# LightLog_SMD_0_7B.net
KiCad netlist of a schematic drawn in EAGLE
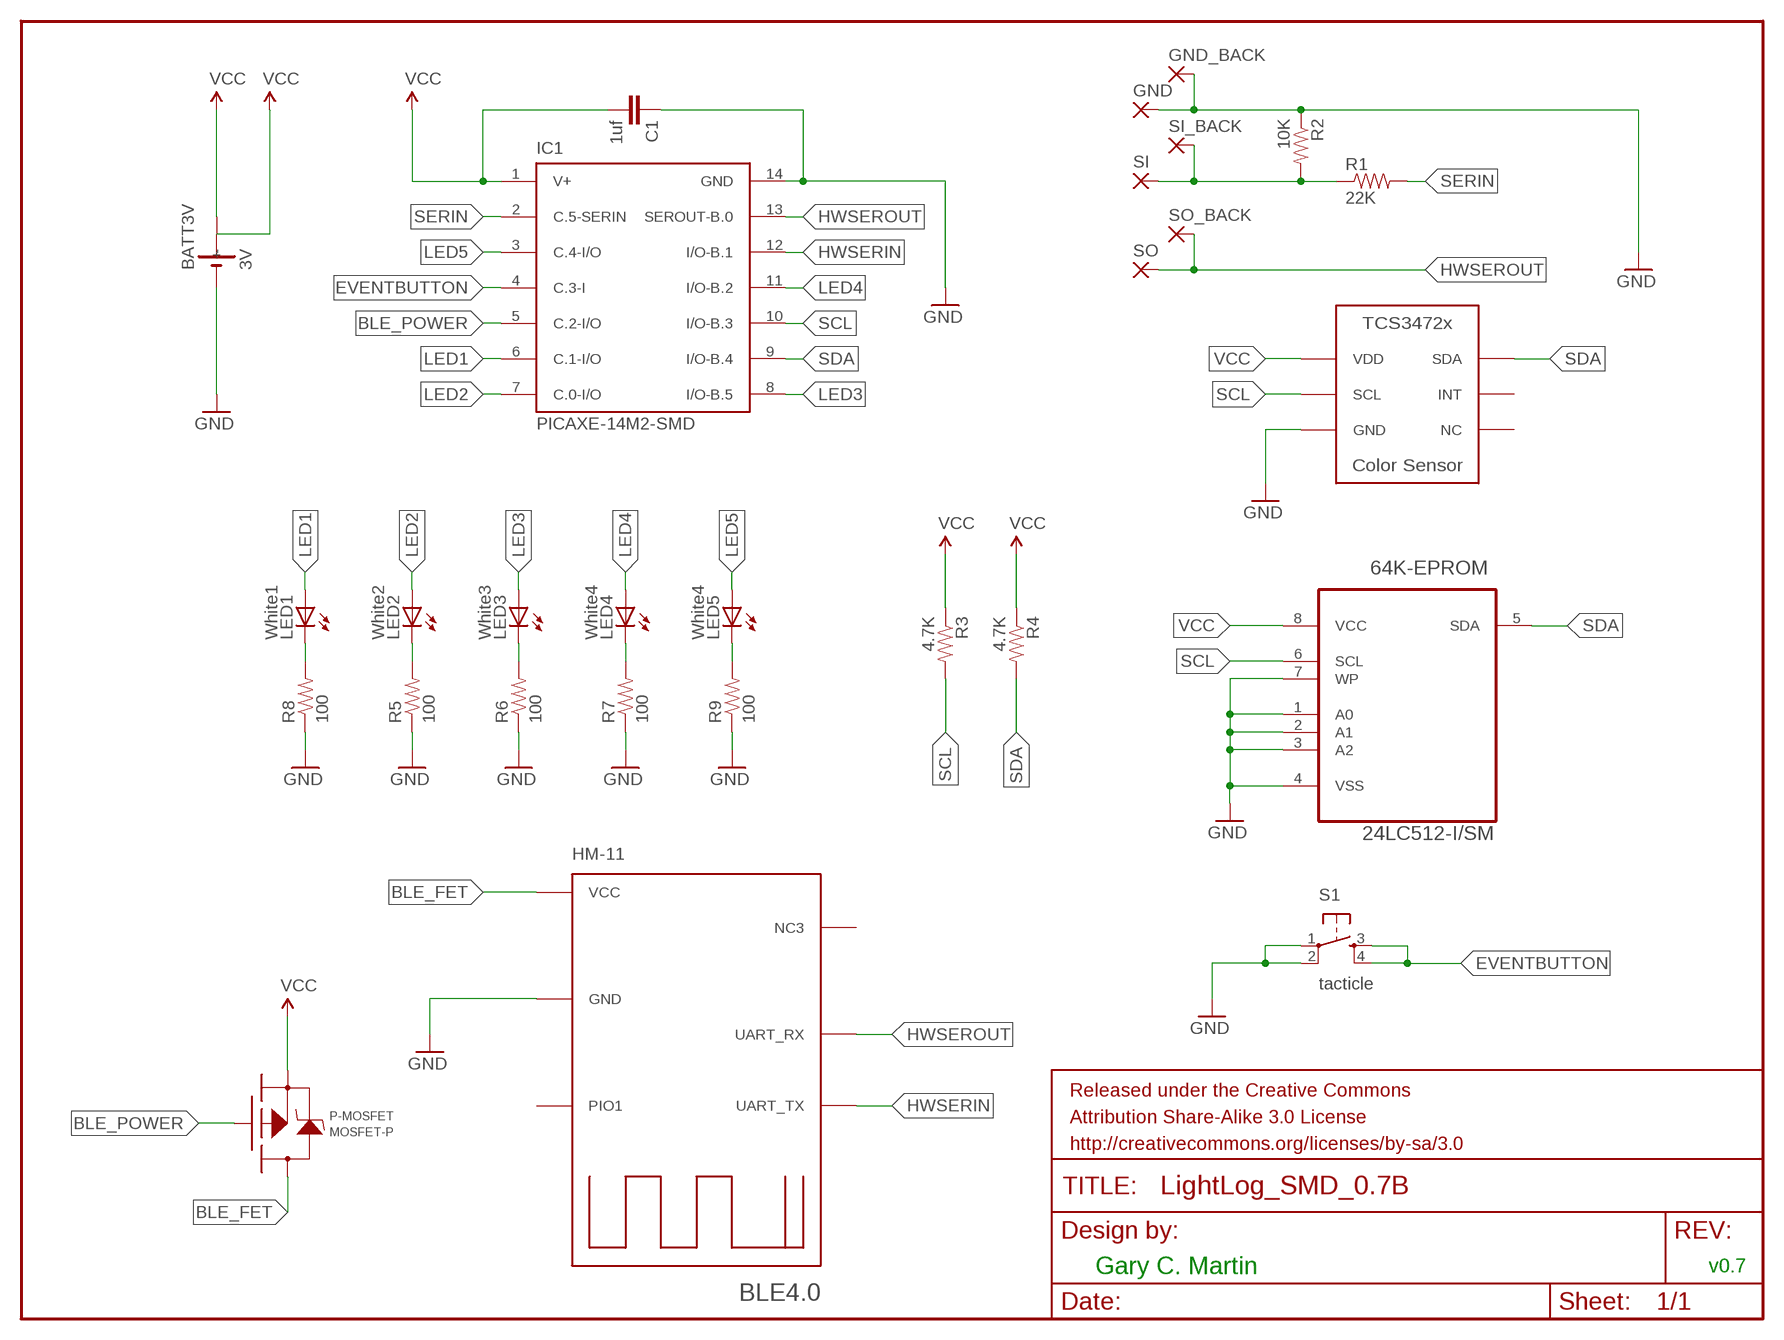
[diagram p0: schematic, sheet 1]

(export (version "E")
  (design (tool "Eeschema 10.0.6"))
  (components
    (comp (ref "64K-EPROM")
      (value "24LC512-I/SM")
      (footprint "eagle-import:SOIC127P794X203-8N")
      (libsource (lib "eagle-import") (part "24LC512-I/SM"))
    )
    (comp (ref "BATT3V")
      (value "3V")
      (footprint "eagle-import:BAT-HLD-001-CR2032-SMD")
      (libsource (lib "eagle-import") (part "BAT-HLD-001-CR2032"))
    )
    (comp (ref "BLE4.0")
      (value "HM-11")
      (footprint "eagle-import:HM-11-MIN")
      (libsource (lib "eagle-import") (part "HM-11-MIN"))
    )
    (comp (ref "C1")
      (value "1uf")
      (footprint "eagle-import:0805")
      (libsource (lib "eagle-import") (part "CAP0805"))
    )
    (comp (ref "GND")
      (value "SMD2")
      (footprint "eagle-import:SMD1,27-2,54")
      (libsource (lib "eagle-import") (part "SMD2"))
    )
    (comp (ref "GND_BACK")
      (value "SMD2")
      (footprint "eagle-import:SMD1,27-2,54")
      (libsource (lib "eagle-import") (part "SMD2"))
    )
    (comp (ref "IC1")
      (value "PICAXE-14M2-SMD")
      (footprint "eagle-import:SOIC14")
      (libsource (lib "eagle-import") (part "PICAXE-14M2-SMD"))
    )
    (comp (ref "LED1")
      (value "White1")
      (footprint "eagle-import:LED-0603")
      (libsource (lib "eagle-import") (part "LED0603"))
    )
    (comp (ref "LED2")
      (value "White2")
      (footprint "eagle-import:LED-0603")
      (libsource (lib "eagle-import") (part "LED0603"))
    )
    (comp (ref "LED3")
      (value "White3")
      (footprint "eagle-import:LED-0603")
      (libsource (lib "eagle-import") (part "LED0603"))
    )
    (comp (ref "LED4")
      (value "White4")
      (footprint "eagle-import:LED-0603")
      (libsource (lib "eagle-import") (part "LED0603"))
    )
    (comp (ref "LED5")
      (value "White4")
      (footprint "eagle-import:LED-0603")
      (libsource (lib "eagle-import") (part "LED0603"))
    )
    (comp (ref "P-MOSFET")
      (value "MOSFET-P")
      (footprint "eagle-import:SOT23-R")
      (libsource (lib "eagle-import") (part "MOSFET-P"))
    )
    (comp (ref "R1")
      (value "22K")
      (footprint "eagle-import:0805")
      (libsource (lib "eagle-import") (part "RESISTOR0805-RES"))
    )
    (comp (ref "R2")
      (value "10K")
      (footprint "eagle-import:0805")
      (libsource (lib "eagle-import") (part "RESISTOR0805-RES"))
    )
    (comp (ref "R3")
      (value "4.7K")
      (footprint "eagle-import:0805")
      (libsource (lib "eagle-import") (part "RESISTOR0805-RES"))
    )
    (comp (ref "R4")
      (value "4.7K")
      (footprint "eagle-import:0805")
      (libsource (lib "eagle-import") (part "RESISTOR0805-RES"))
    )
    (comp (ref "R5")
      (value "100")
      (footprint "eagle-import:0805")
      (libsource (lib "eagle-import") (part "RESISTOR0805-RES"))
    )
    (comp (ref "R6")
      (value "100")
      (footprint "eagle-import:0805")
      (libsource (lib "eagle-import") (part "RESISTOR0805-RES"))
    )
    (comp (ref "R7")
      (value "100")
      (footprint "eagle-import:0805")
      (libsource (lib "eagle-import") (part "RESISTOR0805-RES"))
    )
    (comp (ref "R8")
      (value "100")
      (footprint "eagle-import:0805")
      (libsource (lib "eagle-import") (part "RESISTOR0805-RES"))
    )
    (comp (ref "R9")
      (value "100")
      (footprint "eagle-import:0805")
      (libsource (lib "eagle-import") (part "RESISTOR0805-RES"))
    )
    (comp (ref "S1")
      (value "tacticle")
      (footprint "eagle-import:TACTILE_SWITCH_SMD")
      (libsource (lib "eagle-import") (part "TAC_SWITCHSMD"))
    )
    (comp (ref "SI")
      (value "SMD2")
      (footprint "eagle-import:SMD1,27-2,54")
      (libsource (lib "eagle-import") (part "SMD2"))
    )
    (comp (ref "SI_BACK")
      (value "SMD2")
      (footprint "eagle-import:SMD1,27-2,54")
      (libsource (lib "eagle-import") (part "SMD2"))
    )
    (comp (ref "SO")
      (value "SMD2")
      (footprint "eagle-import:SMD1,27-2,54")
      (libsource (lib "eagle-import") (part "SMD2"))
    )
    (comp (ref "SO_BACK")
      (value "SMD2")
      (footprint "eagle-import:SMD1,27-2,54")
      (libsource (lib "eagle-import") (part "SMD2"))
    )
    (comp (ref "U$1")
      (value "TCS3472")
      (footprint "eagle-import:DUAL-FLAT-NO-LEAD-6PIN")
      (libsource (lib "eagle-import") (part "TCS3472"))
    )
  )
  (nets
    (net (code "1") (name "BLE_FET") (class "Default")
      (node (ref "BLE4.0") (pin "VCC") (pinfunction "VCC_VCC") (pintype "bidirectional"))
      (node (ref "P-MOSFET") (pin "3") (pinfunction "D_3") (pintype "passive"))
    )
    (net (code "2") (name "BLE_POWER") (class "Default")
      (node (ref "IC1") (pin "5") (pinfunction "C.2-I/O_5") (pintype "bidirectional"))
      (node (ref "P-MOSFET") (pin "1") (pinfunction "G_1") (pintype "passive"))
    )
    (net (code "3") (name "EVENTBUTTON") (class "Default")
      (node (ref "IC1") (pin "4") (pinfunction "C.3-I_4") (pintype "input"))
      (node (ref "S1") (pin "3") (pinfunction "3_3") (pintype "passive"))
      (node (ref "S1") (pin "4") (pinfunction "4_4") (pintype "passive"))
    )
    (net (code "4") (name "GND") (class "Default")
      (node (ref "64K-EPROM") (pin "1") (pinfunction "A0_1") (pintype "input"))
      (node (ref "64K-EPROM") (pin "2") (pinfunction "A1_2") (pintype "input"))
      (node (ref "64K-EPROM") (pin "3") (pinfunction "A2_3") (pintype "input"))
      (node (ref "64K-EPROM") (pin "4") (pinfunction "VSS_4") (pintype "passive"))
      (node (ref "64K-EPROM") (pin "7") (pinfunction "WP_7") (pintype "input"))
      (node (ref "BATT3V") (pin "NEG") (pinfunction "-_NEG") (pintype "passive"))
      (node (ref "BLE4.0") (pin "GND") (pinfunction "GND_GND") (pintype "bidirectional"))
      (node (ref "C1") (pin "1") (pinfunction "1_1") (pintype "passive"))
      (node (ref "GND") (pin "1") (pinfunction "P_1") (pintype "passive"))
      (node (ref "GND_BACK") (pin "1") (pinfunction "P_1") (pintype "passive"))
      (node (ref "IC1") (pin "14") (pinfunction "GND_14") (pintype "power_in"))
      (node (ref "R2") (pin "1") (pinfunction "1_1") (pintype "passive"))
      (node (ref "R5") (pin "1") (pinfunction "1_1") (pintype "passive"))
      (node (ref "R6") (pin "1") (pinfunction "1_1") (pintype "passive"))
      (node (ref "R7") (pin "1") (pinfunction "1_1") (pintype "passive"))
      (node (ref "R8") (pin "1") (pinfunction "1_1") (pintype "passive"))
      (node (ref "R9") (pin "1") (pinfunction "1_1") (pintype "passive"))
      (node (ref "S1") (pin "1") (pinfunction "1_1") (pintype "passive"))
      (node (ref "S1") (pin "2") (pinfunction "2_2") (pintype "passive"))
      (node (ref "U$1") (pin "3") (pinfunction "GND_3") (pintype "bidirectional"))
    )
    (net (code "5") (name "HWSERIN") (class "Default")
      (node (ref "BLE4.0") (pin "UART_TX") (pinfunction "UART_TX_UART_TX") (pintype "bidirectional"))
      (node (ref "IC1") (pin "12") (pinfunction "I/O-B.1_12") (pintype "bidirectional"))
    )
    (net (code "6") (name "HWSEROUT") (class "Default")
      (node (ref "BLE4.0") (pin "UART_RX") (pinfunction "UART_RX_UART_RX") (pintype "bidirectional"))
      (node (ref "IC1") (pin "13") (pinfunction "SEROUT-B.0_13") (pintype "output"))
      (node (ref "SO") (pin "1") (pinfunction "P_1") (pintype "passive"))
      (node (ref "SO_BACK") (pin "1") (pinfunction "P_1") (pintype "passive"))
    )
    (net (code "7") (name "LED1") (class "Default")
      (node (ref "IC1") (pin "6") (pinfunction "C.1-I/O_6") (pintype "bidirectional"))
      (node (ref "LED1") (pin "A") (pinfunction "A_A") (pintype "passive"))
    )
    (net (code "8") (name "LED2") (class "Default")
      (node (ref "IC1") (pin "7") (pinfunction "C.0-I/O_7") (pintype "bidirectional"))
      (node (ref "LED2") (pin "A") (pinfunction "A_A") (pintype "passive"))
    )
    (net (code "9") (name "LED3") (class "Default")
      (node (ref "IC1") (pin "8") (pinfunction "I/O-B.5_8") (pintype "bidirectional"))
      (node (ref "LED3") (pin "A") (pinfunction "A_A") (pintype "passive"))
    )
    (net (code "10") (name "LED4") (class "Default")
      (node (ref "IC1") (pin "11") (pinfunction "I/O-B.2_11") (pintype "bidirectional"))
      (node (ref "LED4") (pin "A") (pinfunction "A_A") (pintype "passive"))
    )
    (net (code "11") (name "LED5") (class "Default")
      (node (ref "IC1") (pin "3") (pinfunction "C.4-I/O_3") (pintype "bidirectional"))
      (node (ref "LED5") (pin "A") (pinfunction "A_A") (pintype "passive"))
    )
    (net (code "12") (name "Net-(LED1-PadC)") (class "Default")
      (node (ref "LED1") (pin "C") (pinfunction "C_C") (pintype "passive"))
      (node (ref "R8") (pin "2") (pinfunction "2_2") (pintype "passive"))
    )
    (net (code "13") (name "Net-(LED2-PadC)") (class "Default")
      (node (ref "LED2") (pin "C") (pinfunction "C_C") (pintype "passive"))
      (node (ref "R5") (pin "2") (pinfunction "2_2") (pintype "passive"))
    )
    (net (code "14") (name "Net-(LED3-PadC)") (class "Default")
      (node (ref "LED3") (pin "C") (pinfunction "C_C") (pintype "passive"))
      (node (ref "R6") (pin "2") (pinfunction "2_2") (pintype "passive"))
    )
    (net (code "15") (name "Net-(LED4-PadC)") (class "Default")
      (node (ref "LED4") (pin "C") (pinfunction "C_C") (pintype "passive"))
      (node (ref "R7") (pin "2") (pinfunction "2_2") (pintype "passive"))
    )
    (net (code "16") (name "Net-(LED5-PadC)") (class "Default")
      (node (ref "LED5") (pin "C") (pinfunction "C_C") (pintype "passive"))
      (node (ref "R9") (pin "2") (pinfunction "2_2") (pintype "passive"))
    )
    (net (code "17") (name "Net-(SI-P)") (class "Default")
      (node (ref "R1") (pin "1") (pinfunction "1_1") (pintype "passive"))
      (node (ref "R2") (pin "2") (pinfunction "2_2") (pintype "passive"))
      (node (ref "SI") (pin "1") (pinfunction "P_1") (pintype "passive"))
      (node (ref "SI_BACK") (pin "1") (pinfunction "P_1") (pintype "passive"))
    )
    (net (code "18") (name "SCL") (class "Default")
      (node (ref "64K-EPROM") (pin "6") (pinfunction "SCL_6") (pintype "input"))
      (node (ref "IC1") (pin "10") (pinfunction "I/O-B.3_10") (pintype "bidirectional"))
      (node (ref "R3") (pin "2") (pinfunction "2_2") (pintype "passive"))
      (node (ref "U$1") (pin "2") (pinfunction "SCL_2") (pintype "bidirectional"))
    )
    (net (code "19") (name "SDA") (class "Default")
      (node (ref "64K-EPROM") (pin "5") (pinfunction "SDA_5") (pintype "bidirectional"))
      (node (ref "IC1") (pin "9") (pinfunction "I/O-B.4_9") (pintype "bidirectional"))
      (node (ref "R4") (pin "2") (pinfunction "2_2") (pintype "passive"))
      (node (ref "U$1") (pin "6") (pinfunction "SDA_6") (pintype "bidirectional"))
    )
    (net (code "20") (name "SERIN") (class "Default")
      (node (ref "IC1") (pin "2") (pinfunction "C.5-SERIN_2") (pintype "input"))
      (node (ref "R1") (pin "2") (pinfunction "2_2") (pintype "passive"))
    )
    (net (code "21") (name "VCC") (class "Default")
      (node (ref "64K-EPROM") (pin "8") (pinfunction "VCC_8") (pintype "power_in"))
      (node (ref "BATT3V") (pin "POS1") (pinfunction "+_POS1") (pintype "passive"))
      (node (ref "BATT3V") (pin "POS2") (pinfunction "+_POS2") (pintype "passive"))
      (node (ref "C1") (pin "2") (pinfunction "2_2") (pintype "passive"))
      (node (ref "IC1") (pin "1") (pinfunction "V+_1") (pintype "power_in"))
      (node (ref "P-MOSFET") (pin "2") (pinfunction "S_2") (pintype "passive"))
      (node (ref "R3") (pin "1") (pinfunction "1_1") (pintype "passive"))
      (node (ref "R4") (pin "1") (pinfunction "1_1") (pintype "passive"))
      (node (ref "U$1") (pin "1") (pinfunction "VDD_1") (pintype "bidirectional"))
    )
    (net (code "22") (name "unconnected-(BLE4.0-PIO1-PadPOI1)") (class "Default")
      (node (ref "BLE4.0") (pin "POI1") (pinfunction "PIO1_POI1") (pintype "bidirectional"))
    )
    (net (code "23") (name "unconnected-(BLE4.0-PadNC3)") (class "Default")
      (node (ref "BLE4.0") (pin "NC3") (pinfunction "NC3_NC3") (pintype "bidirectional"))
    )
    (net (code "24") (name "unconnected-(U$1-INT-Pad5)") (class "Default")
      (node (ref "U$1") (pin "5") (pinfunction "INT_5") (pintype "bidirectional"))
    )
    (net (code "25") (name "unconnected-(U$1-NC-Pad4)") (class "Default")
      (node (ref "U$1") (pin "4") (pinfunction "NC_4") (pintype "bidirectional"))
    )
  )
)
